# Servo-potenciom-3.net
KiCad netlist of a schematic drawn in EAGLE
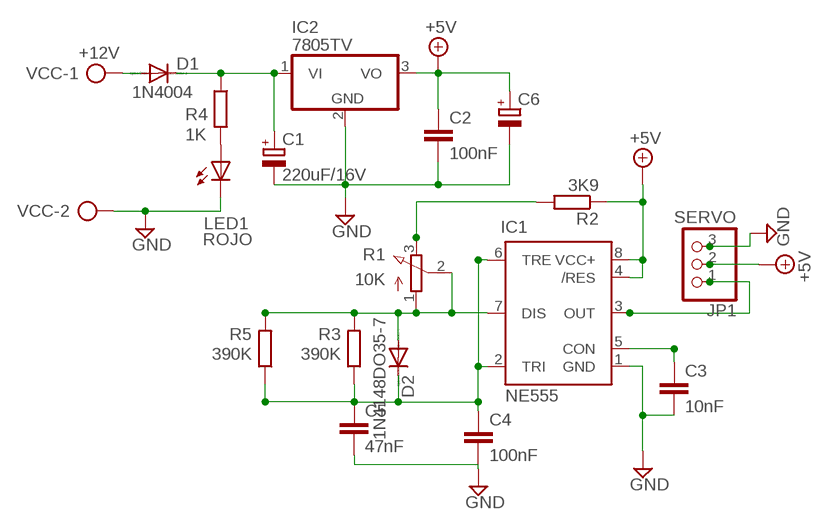
[diagram p0: schematic, sheet 1]

(export (version "E")
  (design (tool "Eeschema 10.0.6"))
  (components
    (comp (ref "C1")
      (value "220uF/16V")
      (footprint "eagle-import:E2,5-7")
      (libsource (lib "eagle-import") (part "CPOL-EUE2.5-7"))
    )
    (comp (ref "C2")
      (value "100nF")
      (footprint "eagle-import:C050-025X075")
      (libsource (lib "eagle-import") (part "C-EU050-025X075"))
    )
    (comp (ref "C3")
      (value "10nF")
      (footprint "eagle-import:C050-025X075")
      (libsource (lib "eagle-import") (part "C-EU050-025X075"))
    )
    (comp (ref "C4")
      (value "100nF")
      (footprint "eagle-import:C050-025X075")
      (libsource (lib "eagle-import") (part "C-EU050-025X075"))
    )
    (comp (ref "C5")
      (value "47nF")
      (footprint "eagle-import:C050-025X075")
      (libsource (lib "eagle-import") (part "C-EU050-025X075"))
    )
    (comp (ref "C6")
      (value "CPOL-EUE2.5-5")
      (footprint "eagle-import:E2,5-5")
      (libsource (lib "eagle-import") (part "CPOL-EUE2.5-5"))
    )
    (comp (ref "D1")
      (value "1N4004")
      (footprint "eagle-import:DO41-10")
      (libsource (lib "eagle-import") (part "1N4004"))
    )
    (comp (ref "D2")
      (value "1N4148DO35-7")
      (footprint "eagle-import:DO35-7")
      (libsource (lib "eagle-import") (part "1N4148DO35-7"))
    )
    (comp (ref "IC1")
      (value "NE555")
      (footprint "eagle-import:DIL-08")
      (fields (field (name "MF") "Arrow Electronics") (field (name "MPN") "NE555N"))
      (libsource (lib "eagle-import") (part "NE555"))
    )
    (comp (ref "IC2")
      (value "7805TV")
      (footprint "eagle-import:TO220V")
      (libsource (lib "eagle-import") (part "78TV05"))
    )
    (comp (ref "JP1")
      (value "SERVO")
      (footprint "eagle-import:1X03")
      (libsource (lib "eagle-import") (part "PINHD-1X3"))
    )
    (comp (ref "LED1")
      (value "ROJO")
      (footprint "eagle-import:LED3MM")
      (libsource (lib "eagle-import") (part "LED3MM"))
    )
    (comp (ref "R1")
      (value "10K")
      (footprint "eagle-import:3RP_1610N")
      (libsource (lib "eagle-import") (part "3RP/1610N"))
    )
    (comp (ref "R2")
      (value "3K9")
      (footprint "eagle-import:0207_10")
      (libsource (lib "eagle-import") (part "R-EU_0207/10"))
    )
    (comp (ref "R3")
      (value "390K")
      (footprint "eagle-import:0207_10")
      (libsource (lib "eagle-import") (part "R-EU_0207/10"))
    )
    (comp (ref "R4")
      (value "1K")
      (footprint "eagle-import:0207_10")
      (libsource (lib "eagle-import") (part "R-EU_0207/10"))
    )
    (comp (ref "R5")
      (value "390K")
      (footprint "eagle-import:0207_10")
      (libsource (lib "eagle-import") (part "R-EU_0207/10"))
    )
    (comp (ref "VCC")
      (value "+12V")
      (footprint "eagle-import:AK500_2-H")
      (libsource (lib "eagle-import") (part "AK500/2-H"))
    )
  )
  (nets
    (net (code "1") (name "+5V") (class "Default")
      (node (ref "C2") (pin "1") (pinfunction "1_1") (pintype "passive"))
      (node (ref "C6") (pin "+") (pinfunction "+_+") (pintype "passive"))
      (node (ref "IC1") (pin "4") (pinfunction "/RES_4") (pintype "input"))
      (node (ref "IC1") (pin "8") (pinfunction "VCC+_8") (pintype "power_in"))
      (node (ref "IC2") (pin "3") (pinfunction "VO_3") (pintype "passive"))
      (node (ref "JP1") (pin "2") (pinfunction "2_2") (pintype "passive"))
      (node (ref "R2") (pin "1") (pinfunction "1_1") (pintype "passive"))
    )
    (net (code "2") (name "GND") (class "Default")
      (node (ref "C1") (pin "-") (pinfunction "-_-") (pintype "passive"))
      (node (ref "C2") (pin "2") (pinfunction "2_2") (pintype "passive"))
      (node (ref "C3") (pin "2") (pinfunction "2_2") (pintype "passive"))
      (node (ref "C4") (pin "2") (pinfunction "2_2") (pintype "passive"))
      (node (ref "C5") (pin "2") (pinfunction "2_2") (pintype "passive"))
      (node (ref "C6") (pin "-") (pinfunction "-_-") (pintype "passive"))
      (node (ref "IC1") (pin "1") (pinfunction "GND_1") (pintype "power_in"))
      (node (ref "IC2") (pin "2") (pinfunction "GND_2") (pintype "passive"))
      (node (ref "JP1") (pin "3") (pinfunction "3_3") (pintype "passive"))
      (node (ref "LED1") (pin "K") (pinfunction "C_K") (pintype "passive"))
      (node (ref "VCC") (pin "2") (pinfunction "KL_2") (pintype "passive"))
    )
    (net (code "3") (name "Net-(IC1-CON)") (class "Default")
      (node (ref "C3") (pin "1") (pinfunction "1_1") (pintype "passive"))
      (node (ref "IC1") (pin "5") (pinfunction "CON_5") (pintype "input"))
    )
    (net (code "4") (name "Net-(IC1-DIS)") (class "Default")
      (node (ref "D2") (pin "A") (pinfunction "A_A") (pintype "passive"))
      (node (ref "IC1") (pin "7") (pinfunction "DIS_7") (pintype "input"))
      (node (ref "R1") (pin "1") (pinfunction "A_1") (pintype "passive"))
      (node (ref "R1") (pin "2") (pinfunction "S_2") (pintype "passive"))
      (node (ref "R3") (pin "2") (pinfunction "2_2") (pintype "passive"))
      (node (ref "R5") (pin "2") (pinfunction "2_2") (pintype "passive"))
    )
    (net (code "5") (name "Net-(IC1-OUT)") (class "Default")
      (node (ref "IC1") (pin "3") (pinfunction "OUT_3") (pintype "output"))
      (node (ref "JP1") (pin "1") (pinfunction "1_1") (pintype "passive"))
    )
    (net (code "6") (name "Net-(IC1-TRE)") (class "Default")
      (node (ref "C4") (pin "1") (pinfunction "1_1") (pintype "passive"))
      (node (ref "C5") (pin "1") (pinfunction "1_1") (pintype "passive"))
      (node (ref "D2") (pin "C") (pinfunction "C_C") (pintype "passive"))
      (node (ref "IC1") (pin "2") (pinfunction "TRI_2") (pintype "input"))
      (node (ref "IC1") (pin "6") (pinfunction "TRE_6") (pintype "input"))
      (node (ref "R3") (pin "1") (pinfunction "1_1") (pintype "passive"))
      (node (ref "R5") (pin "1") (pinfunction "1_1") (pintype "passive"))
    )
    (net (code "7") (name "Net-(IC2-VI)") (class "Default")
      (node (ref "C1") (pin "+") (pinfunction "+_+") (pintype "passive"))
      (node (ref "D1") (pin "C") (pinfunction "C_C") (pintype "passive"))
      (node (ref "IC2") (pin "1") (pinfunction "VI_1") (pintype "input"))
      (node (ref "R4") (pin "1") (pinfunction "1_1") (pintype "passive"))
    )
    (net (code "8") (name "Net-(LED1-PadA)") (class "Default")
      (node (ref "LED1") (pin "A") (pinfunction "A_A") (pintype "passive"))
      (node (ref "R4") (pin "2") (pinfunction "2_2") (pintype "passive"))
    )
    (net (code "9") (name "Net-(R1-E)") (class "Default")
      (node (ref "R1") (pin "3") (pinfunction "E_3") (pintype "passive"))
      (node (ref "R2") (pin "2") (pinfunction "2_2") (pintype "passive"))
    )
    (net (code "10") (name "Net-(VCCA-KL)") (class "Default")
      (node (ref "D1") (pin "A") (pinfunction "A_A") (pintype "passive"))
      (node (ref "VCC") (pin "1") (pinfunction "KL_1") (pintype "passive"))
    )
  )
)
